# T15_PRI_SYS_V1_1.net
KiCad netlist of a schematic drawn in EAGLE
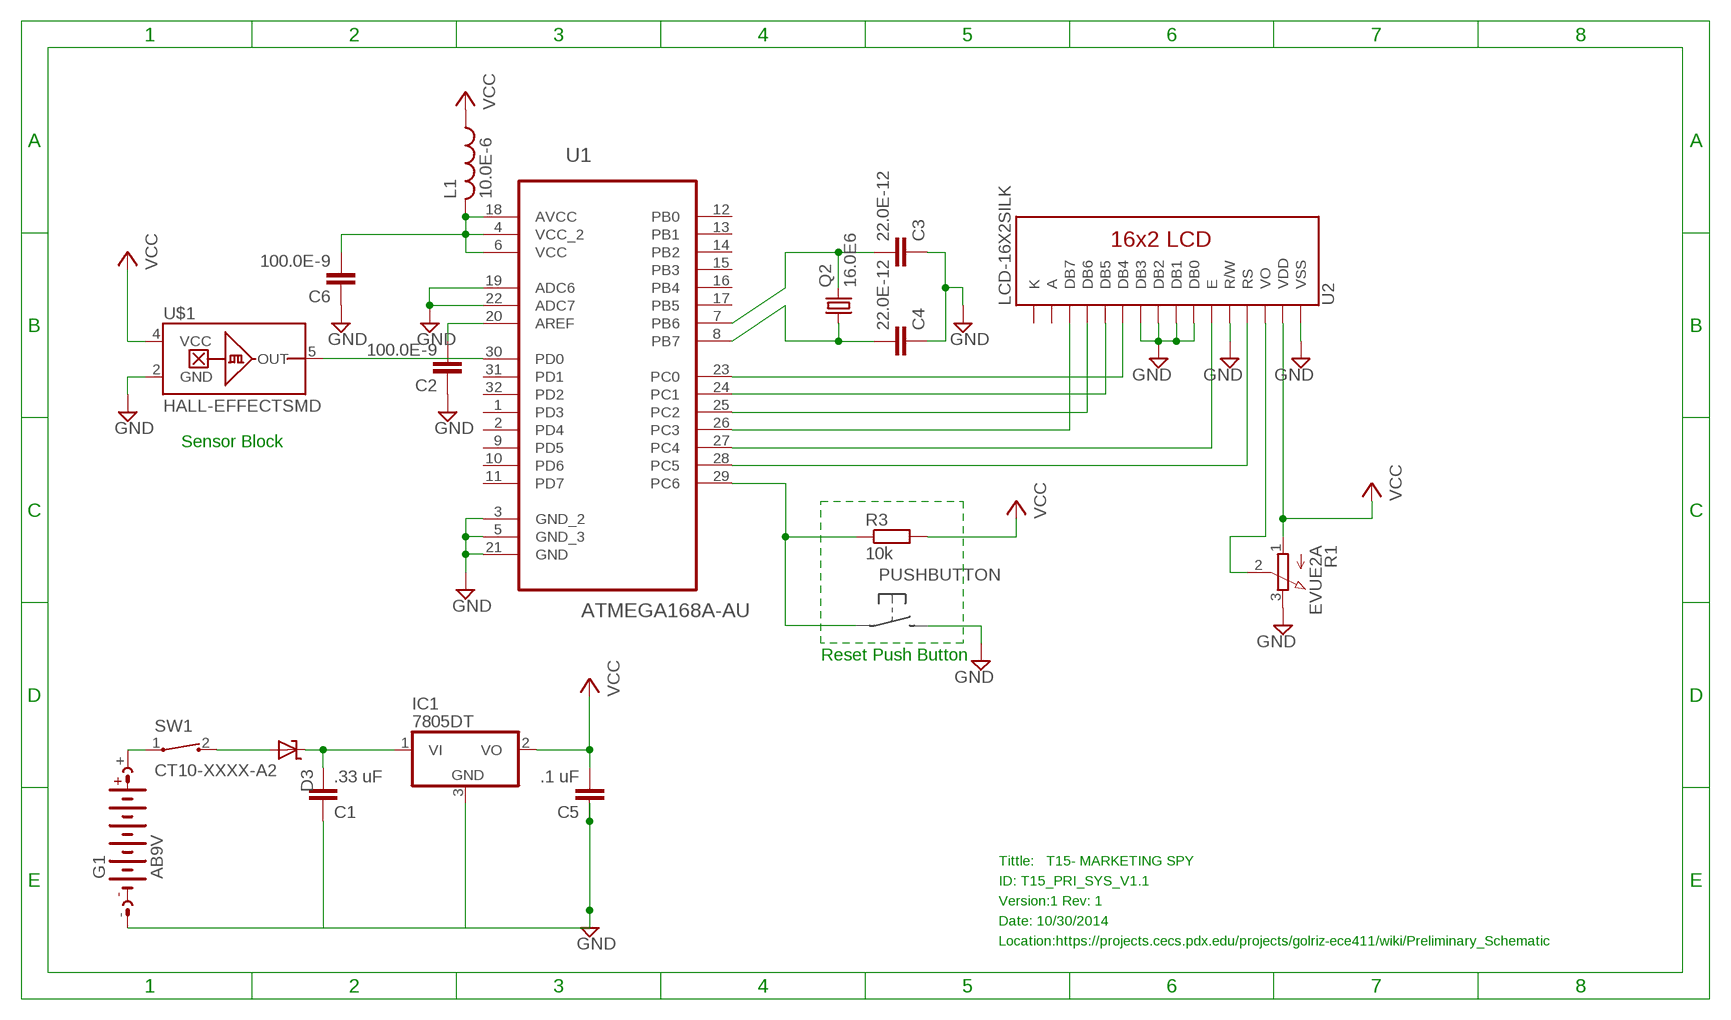
[diagram p0: schematic, sheet 1]

(export (version "E")
  (design (tool "Eeschema 10.0.6"))
  (components
    (comp (ref "C1")
      (value ".33 uF")
      (footprint "eagle-import:C025-024X044")
      (libsource (lib "eagle-import") (part "C-EU025-024X044"))
    )
    (comp (ref "C2")
      (value "100.0E-9")
      (footprint "eagle-import:C025-024X044")
      (libsource (lib "eagle-import") (part "C-EU025-024X044"))
    )
    (comp (ref "C3")
      (value "22.0E-12")
      (footprint "eagle-import:C025-024X044")
      (libsource (lib "eagle-import") (part "C-EU025-024X044"))
    )
    (comp (ref "C4")
      (value "22.0E-12")
      (footprint "eagle-import:C025-024X044")
      (libsource (lib "eagle-import") (part "C-EU025-024X044"))
    )
    (comp (ref "C5")
      (value ".1 uF")
      (footprint "eagle-import:C025-024X044")
      (libsource (lib "eagle-import") (part "C-EU025-024X044"))
    )
    (comp (ref "C6")
      (value "100.0E-9")
      (footprint "eagle-import:C025-024X044")
      (libsource (lib "eagle-import") (part "C-EU025-024X044"))
    )
    (comp (ref "D3")
      (value "SUPPRESSOR-SMBJ")
      (footprint "eagle-import:SMBJ")
      (libsource (lib "eagle-import") (part "SUPPRESSOR-SMBJ"))
    )
    (comp (ref "G1")
      (value "AB9V")
      (footprint "eagle-import:AB9V")
      (libsource (lib "eagle-import") (part "AB9V"))
    )
    (comp (ref "IC1")
      (value "7805DT")
      (footprint "eagle-import:TO252")
      (libsource (lib "eagle-import") (part "78DT05"))
    )
    (comp (ref "L1")
      (value "10.0E-6")
      (footprint "eagle-import:0204_5")
      (libsource (lib "eagle-import") (part "L-US0204/5"))
    )
    (comp (ref "Q2")
      (value "16.0E6")
      (footprint "eagle-import:HC49_S")
      (libsource (lib "eagle-import") (part "CRYSTALHC49S"))
    )
    (comp (ref "R1")
      (value "EVUE2A")
      (footprint "eagle-import:EVUE")
      (libsource (lib "eagle-import") (part "EVUE2A"))
    )
    (comp (ref "R3")
      (value "10k")
      (footprint "eagle-import:0204_5")
      (libsource (lib "eagle-import") (part "R-EU_0204/5"))
    )
    (comp (ref "SW1")
      (value "CT10-XXXX-A2")
      (footprint "eagle-import:CT10-XXXX-A2")
      (libsource (lib "eagle-import") (part "CT10-XXXX-A2"))
    )
    (comp (ref "U$1")
      (value "HALL-EFFECTSMD")
      (footprint "eagle-import:SC70")
      (libsource (lib "eagle-import") (part "HALL-EFFECTSMD"))
    )
    (comp (ref "U1")
      (value "ATMEGA168A-AU")
      (footprint "eagle-import:QFP80P900X900X120-32N")
      (libsource (lib "eagle-import") (part "ATMEGA168A-AU"))
    )
    (comp (ref "U2")
      (value "LCD-16X2SILK")
      (footprint "eagle-import:LCD-16X2")
      (libsource (lib "eagle-import") (part "LCD-16X2SILK"))
    )
  )
  (nets
    (net (code "1") (name "/A") (class "Default")
      (node (ref "U2") (pin "15") (pinfunction "A_15") (pintype "power_in"))
    )
    (net (code "2") (name "/K") (class "Default")
      (node (ref "U2") (pin "16") (pinfunction "K_16") (pintype "power_in"))
    )
    (net (code "3") (name "GND") (class "Default")
      (node (ref "C1") (pin "1") (pinfunction "1_1") (pintype "passive"))
      (node (ref "C2") (pin "1") (pinfunction "1_1") (pintype "passive"))
      (node (ref "C3") (pin "1") (pinfunction "1_1") (pintype "passive"))
      (node (ref "C4") (pin "1") (pinfunction "1_1") (pintype "passive"))
      (node (ref "C5") (pin "1") (pinfunction "1_1") (pintype "passive"))
      (node (ref "C6") (pin "1") (pinfunction "1_1") (pintype "passive"))
      (node (ref "G1") (pin "-") (pinfunction "-_-") (pintype "passive"))
      (node (ref "IC1") (pin "3") (pinfunction "GND_3") (pintype "passive"))
      (node (ref "R1") (pin "3") (pinfunction "E_3") (pintype "passive"))
      (node (ref "U$1") (pin "2") (pinfunction "GND_2") (pintype "bidirectional"))
      (node (ref "U1") (pin "19") (pinfunction "ADC6_19") (pintype "input"))
      (node (ref "U1") (pin "21") (pinfunction "GND_21") (pintype "passive"))
      (node (ref "U1") (pin "22") (pinfunction "ADC7_22") (pintype "input"))
      (node (ref "U1") (pin "3") (pinfunction "GND_2_3") (pintype "passive"))
      (node (ref "U1") (pin "5") (pinfunction "GND_3_5") (pintype "passive"))
      (node (ref "U2") (pin "1") (pinfunction "VSS_1") (pintype "power_in"))
      (node (ref "U2") (pin "10") (pinfunction "DB3_10") (pintype "bidirectional"))
      (node (ref "U2") (pin "5") (pinfunction "R/W_5") (pintype "input"))
      (node (ref "U2") (pin "7") (pinfunction "DB0_7") (pintype "bidirectional"))
      (node (ref "U2") (pin "8") (pinfunction "DB1_8") (pintype "bidirectional"))
      (node (ref "U2") (pin "9") (pinfunction "DB2_9") (pintype "bidirectional"))
    )
    (net (code "4") (name "Net-(D3-PadA)") (class "Default")
      (node (ref "D3") (pin "A") (pinfunction "A_A") (pintype "passive"))
      (node (ref "SW1") (pin "2") (pinfunction "2_2") (pintype "passive"))
    )
    (net (code "5") (name "Net-(G1-Pad+)") (class "Default")
      (node (ref "G1") (pin "+") (pinfunction "+_+") (pintype "passive"))
      (node (ref "SW1") (pin "1") (pinfunction "1_1") (pintype "passive"))
    )
    (net (code "6") (name "Net-(IC1-VI)") (class "Default")
      (node (ref "C1") (pin "2") (pinfunction "2_2") (pintype "passive"))
      (node (ref "D3") (pin "C") (pinfunction "C_C") (pintype "passive"))
      (node (ref "IC1") (pin "1") (pinfunction "VI_1") (pintype "input"))
    )
    (net (code "7") (name "Net-(R1-S)") (class "Default")
      (node (ref "R1") (pin "2") (pinfunction "S_2") (pintype "passive"))
      (node (ref "U2") (pin "3") (pinfunction "VO_3") (pintype "bidirectional"))
    )
    (net (code "8") (name "Net-(U$1-OUT)") (class "Default")
      (node (ref "U$1") (pin "5") (pinfunction "OUT_5") (pintype "bidirectional"))
      (node (ref "U1") (pin "30") (pinfunction "PD0_30") (pintype "bidirectional"))
    )
    (net (code "9") (name "Net-(U1-AREF)") (class "Default")
      (node (ref "C2") (pin "2") (pinfunction "2_2") (pintype "passive"))
      (node (ref "U1") (pin "20") (pinfunction "AREF_20") (pintype "input"))
    )
    (net (code "10") (name "Net-(U1-AVCC)") (class "Default")
      (node (ref "C6") (pin "2") (pinfunction "2_2") (pintype "passive"))
      (node (ref "L1") (pin "2") (pinfunction "2_2") (pintype "passive"))
      (node (ref "U1") (pin "18") (pinfunction "AVCC_18") (pintype "power_in"))
      (node (ref "U1") (pin "4") (pinfunction "VCC_2_4") (pintype "power_in"))
      (node (ref "U1") (pin "6") (pinfunction "VCC_6") (pintype "power_in"))
    )
    (net (code "11") (name "Net-(U1-PB6)") (class "Default")
      (node (ref "C3") (pin "2") (pinfunction "2_2") (pintype "passive"))
      (node (ref "Q2") (pin "2") (pinfunction "2_2") (pintype "passive"))
      (node (ref "U1") (pin "7") (pinfunction "PB6_7") (pintype "bidirectional"))
    )
    (net (code "12") (name "Net-(U1-PB7)") (class "Default")
      (node (ref "C4") (pin "2") (pinfunction "2_2") (pintype "passive"))
      (node (ref "Q2") (pin "1") (pinfunction "1_1") (pintype "passive"))
      (node (ref "U1") (pin "8") (pinfunction "PB7_8") (pintype "bidirectional"))
    )
    (net (code "13") (name "Net-(U1-PC0)") (class "Default")
      (node (ref "U1") (pin "23") (pinfunction "PC0_23") (pintype "bidirectional"))
      (node (ref "U2") (pin "11") (pinfunction "DB4_11") (pintype "bidirectional"))
    )
    (net (code "14") (name "Net-(U1-PC1)") (class "Default")
      (node (ref "U1") (pin "24") (pinfunction "PC1_24") (pintype "bidirectional"))
      (node (ref "U2") (pin "12") (pinfunction "DB5_12") (pintype "bidirectional"))
    )
    (net (code "15") (name "Net-(U1-PC2)") (class "Default")
      (node (ref "U1") (pin "25") (pinfunction "PC2_25") (pintype "bidirectional"))
      (node (ref "U2") (pin "13") (pinfunction "DB6_13") (pintype "bidirectional"))
    )
    (net (code "16") (name "Net-(U1-PC3)") (class "Default")
      (node (ref "U1") (pin "26") (pinfunction "PC3_26") (pintype "bidirectional"))
      (node (ref "U2") (pin "14") (pinfunction "DB7_14") (pintype "bidirectional"))
    )
    (net (code "17") (name "Net-(U1-PC4)") (class "Default")
      (node (ref "U1") (pin "27") (pinfunction "PC4_27") (pintype "bidirectional"))
      (node (ref "U2") (pin "6") (pinfunction "E_6") (pintype "input"))
    )
    (net (code "18") (name "Net-(U1-PC5)") (class "Default")
      (node (ref "U1") (pin "28") (pinfunction "PC5_28") (pintype "bidirectional"))
      (node (ref "U2") (pin "4") (pinfunction "RS_4") (pintype "input"))
    )
    (net (code "19") (name "Net-(U1-PC6)") (class "Default")
      (node (ref "R3") (pin "1") (pinfunction "1_1") (pintype "passive"))
      (node (ref "U1") (pin "29") (pinfunction "PC6_29") (pintype "bidirectional"))
    )
    (net (code "20") (name "VCC") (class "Default")
      (node (ref "C5") (pin "2") (pinfunction "2_2") (pintype "passive"))
      (node (ref "IC1") (pin "2") (pinfunction "VO_2") (pintype "passive"))
      (node (ref "L1") (pin "1") (pinfunction "1_1") (pintype "passive"))
      (node (ref "R1") (pin "1") (pinfunction "A_1") (pintype "passive"))
      (node (ref "R3") (pin "2") (pinfunction "2_2") (pintype "passive"))
      (node (ref "U$1") (pin "4") (pinfunction "VCC_4") (pintype "bidirectional"))
      (node (ref "U2") (pin "2") (pinfunction "VDD_2") (pintype "power_in"))
    )
    (net (code "21") (name "unconnected-(U1-PB0-Pad12)") (class "Default")
      (node (ref "U1") (pin "12") (pinfunction "PB0_12") (pintype "bidirectional"))
    )
    (net (code "22") (name "unconnected-(U1-PB1-Pad13)") (class "Default")
      (node (ref "U1") (pin "13") (pinfunction "PB1_13") (pintype "bidirectional"))
    )
    (net (code "23") (name "unconnected-(U1-PB2-Pad14)") (class "Default")
      (node (ref "U1") (pin "14") (pinfunction "PB2_14") (pintype "bidirectional"))
    )
    (net (code "24") (name "unconnected-(U1-PB3-Pad15)") (class "Default")
      (node (ref "U1") (pin "15") (pinfunction "PB3_15") (pintype "bidirectional"))
    )
    (net (code "25") (name "unconnected-(U1-PB4-Pad16)") (class "Default")
      (node (ref "U1") (pin "16") (pinfunction "PB4_16") (pintype "bidirectional"))
    )
    (net (code "26") (name "unconnected-(U1-PB5-Pad17)") (class "Default")
      (node (ref "U1") (pin "17") (pinfunction "PB5_17") (pintype "bidirectional"))
    )
    (net (code "27") (name "unconnected-(U1-PD1-Pad31)") (class "Default")
      (node (ref "U1") (pin "31") (pinfunction "PD1_31") (pintype "bidirectional"))
    )
    (net (code "28") (name "unconnected-(U1-PD2-Pad32)") (class "Default")
      (node (ref "U1") (pin "32") (pinfunction "PD2_32") (pintype "bidirectional"))
    )
    (net (code "29") (name "unconnected-(U1-PD3-Pad1)") (class "Default")
      (node (ref "U1") (pin "1") (pinfunction "PD3_1") (pintype "bidirectional"))
    )
    (net (code "30") (name "unconnected-(U1-PD4-Pad2)") (class "Default")
      (node (ref "U1") (pin "2") (pinfunction "PD4_2") (pintype "bidirectional"))
    )
    (net (code "31") (name "unconnected-(U1-PD5-Pad9)") (class "Default")
      (node (ref "U1") (pin "9") (pinfunction "PD5_9") (pintype "bidirectional"))
    )
    (net (code "32") (name "unconnected-(U1-PD6-Pad10)") (class "Default")
      (node (ref "U1") (pin "10") (pinfunction "PD6_10") (pintype "bidirectional"))
    )
    (net (code "33") (name "unconnected-(U1-PD7-Pad11)") (class "Default")
      (node (ref "U1") (pin "11") (pinfunction "PD7_11") (pintype "bidirectional"))
    )
  )
)
